# skyboard.net
KiCad netlist of a schematic drawn in EAGLE
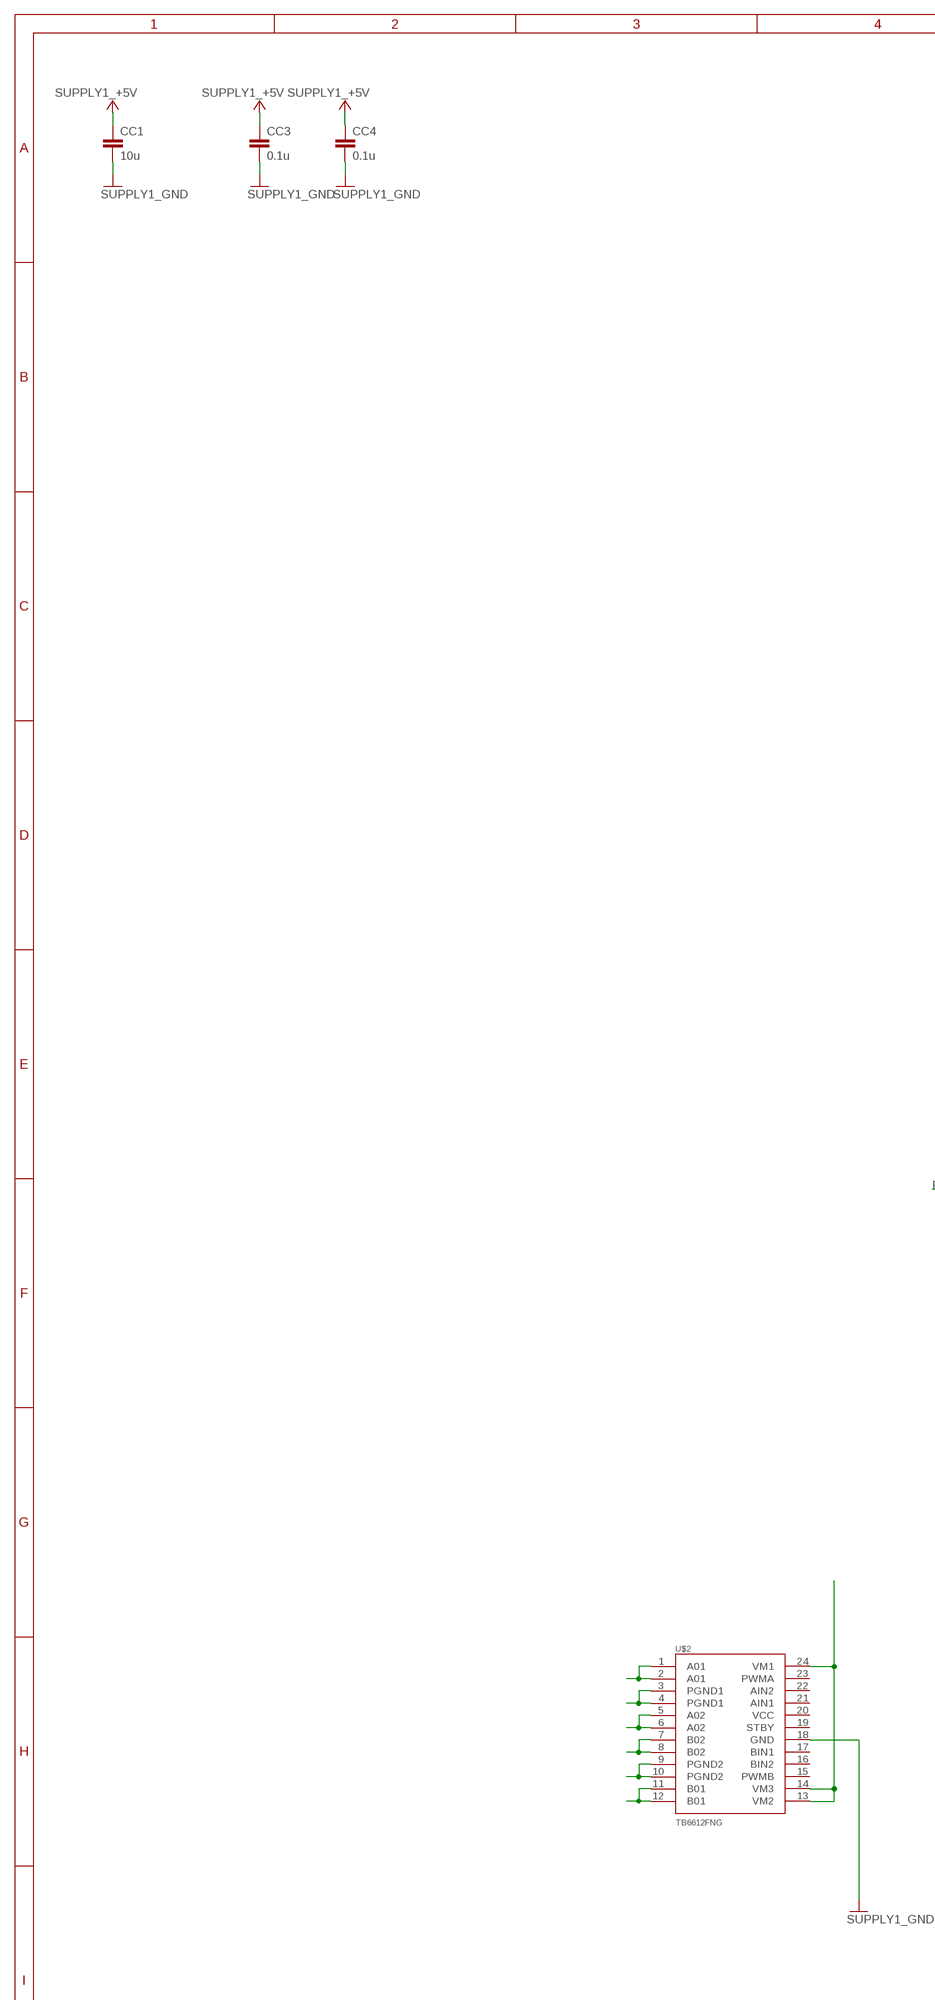
[diagram p0: schematic, sheet 1, part 1 of 2]
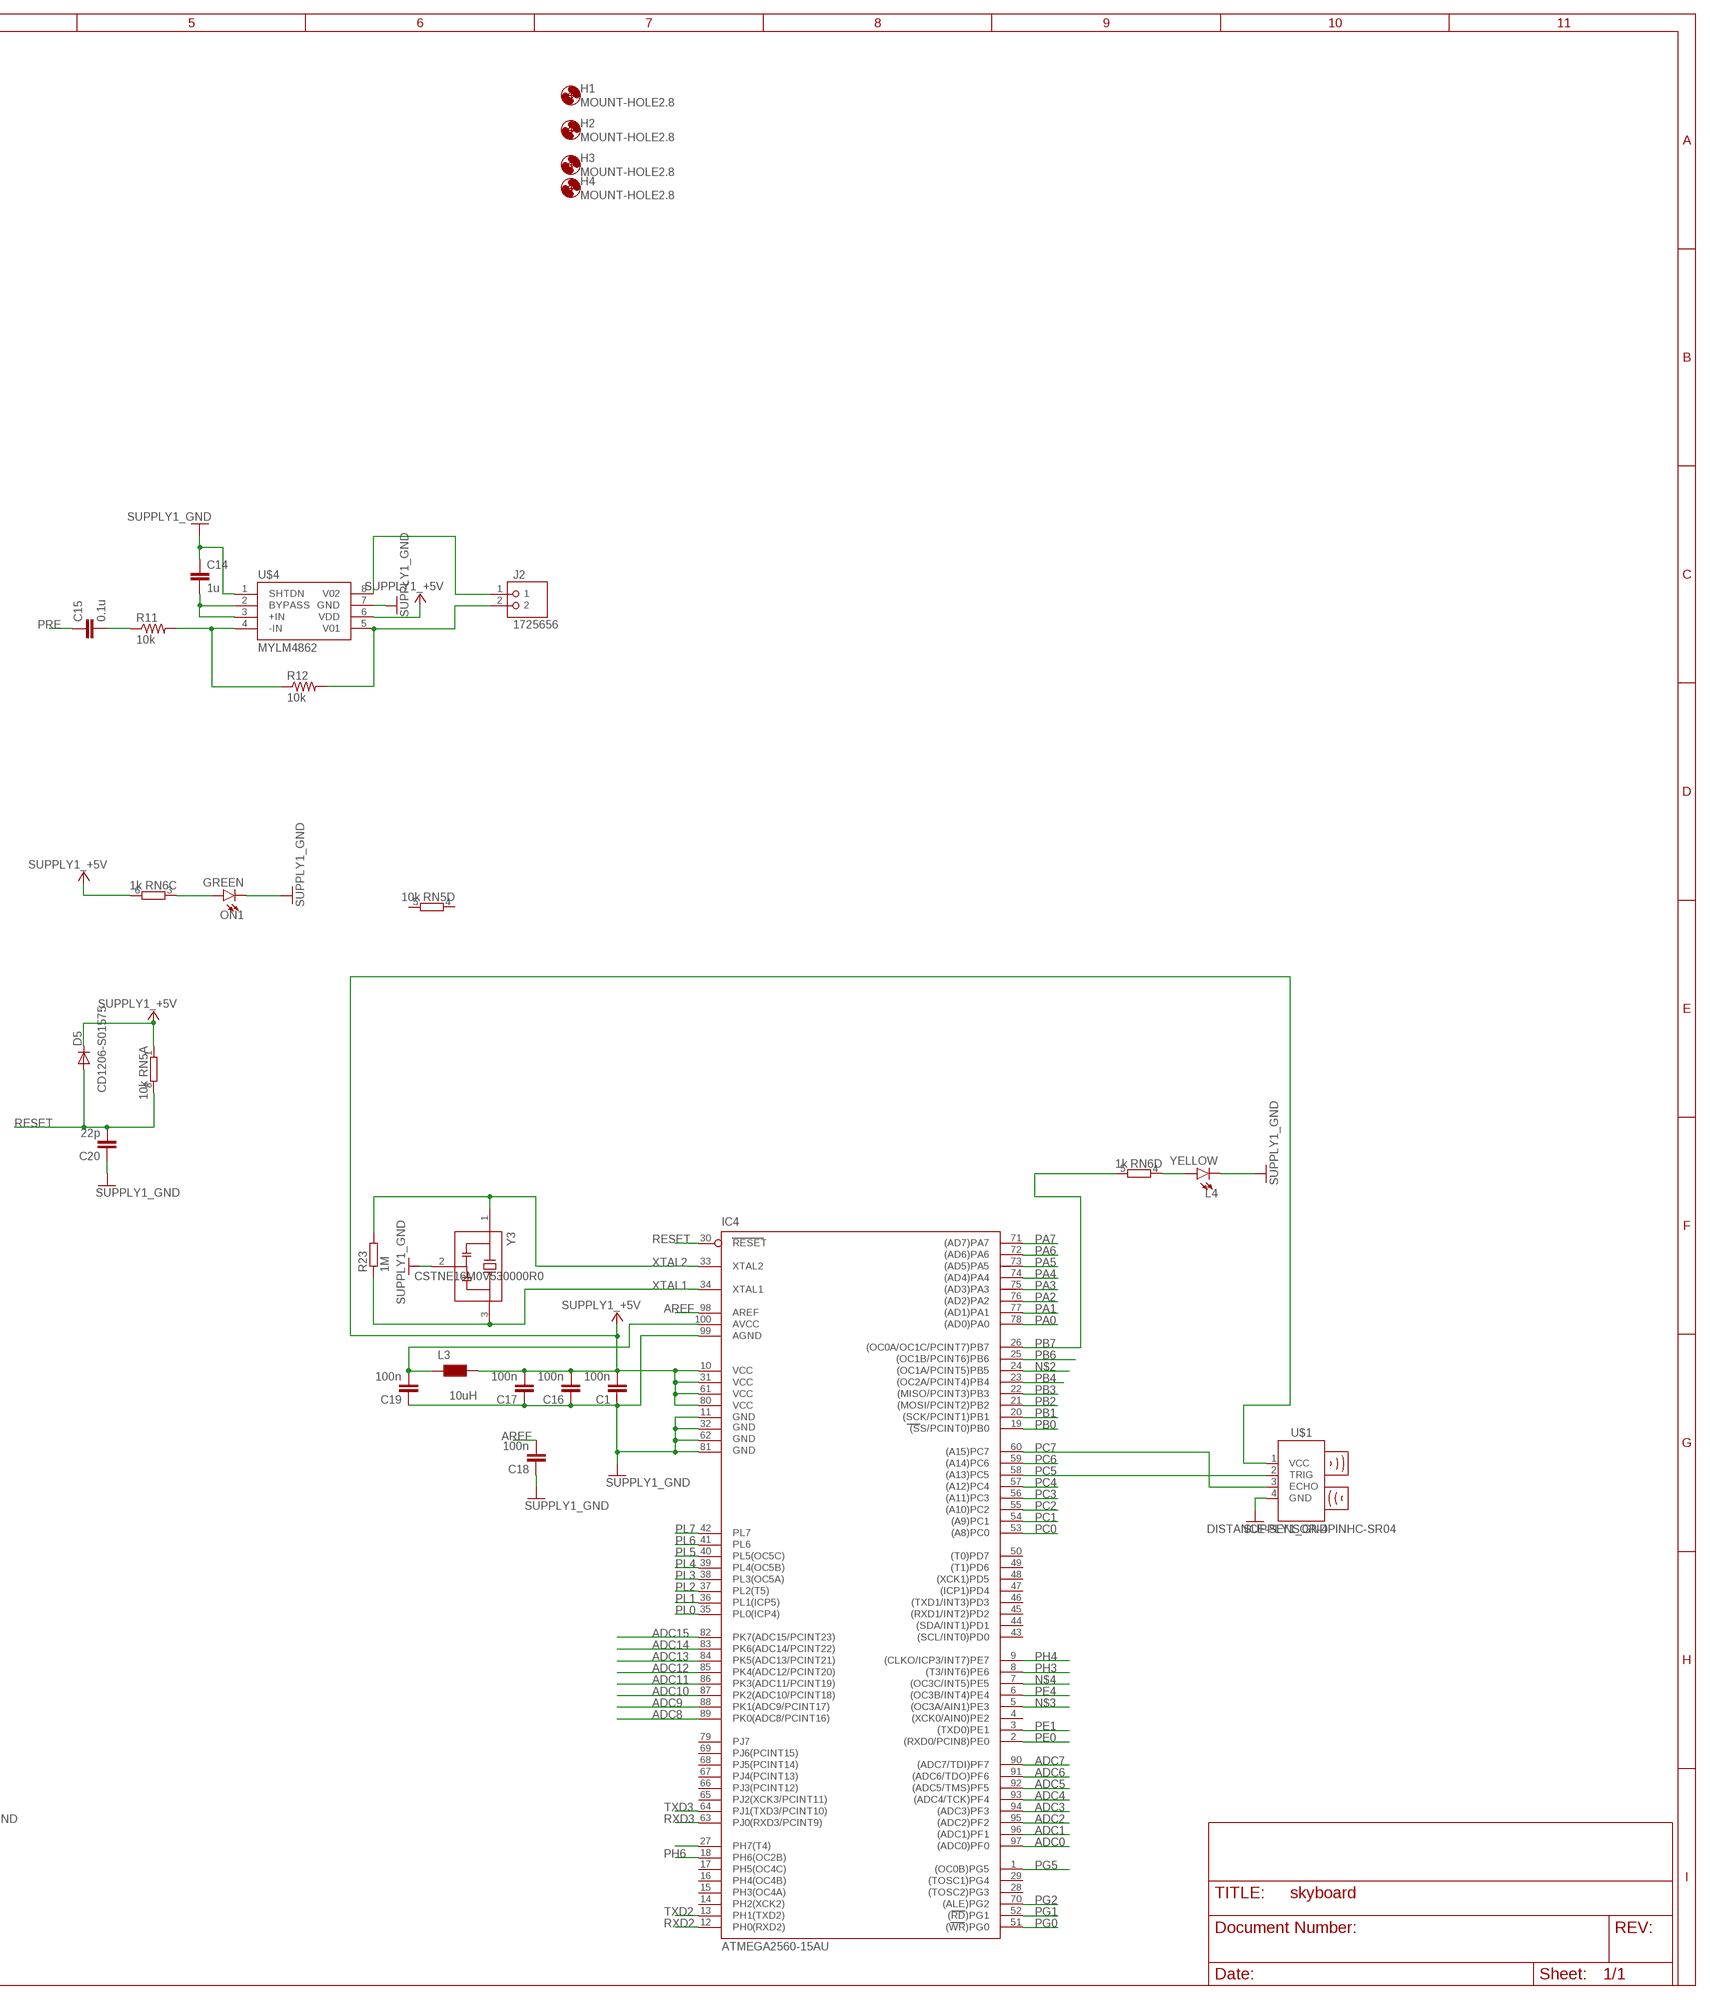
[diagram p1: schematic, sheet 1, part 2 of 2]

(export (version "E")
  (design (tool "Eeschema 10.0.6"))
  (components
    (comp (ref "C1")
      (value "100n")
      (footprint "eagle-import:SMARTPRJ_C1206")
      (libsource (lib "eagle-import") (part "SMARTPRJ_C-EUC1206"))
    )
    (comp (ref "C14")
      (value "1u")
      (footprint "eagle-import:SMARTPRJ_C1206")
      (libsource (lib "eagle-import") (part "SMARTPRJ_C-EUC1206"))
    )
    (comp (ref "C15")
      (value "0.1u")
      (footprint "eagle-import:SMARTPRJ_C1206")
      (libsource (lib "eagle-import") (part "SMARTPRJ_C-EUC1206"))
    )
    (comp (ref "C16")
      (value "100n")
      (footprint "eagle-import:SMARTPRJ_C1206")
      (libsource (lib "eagle-import") (part "SMARTPRJ_C-EUC1206"))
    )
    (comp (ref "C17")
      (value "100n")
      (footprint "eagle-import:SMARTPRJ_C1206")
      (libsource (lib "eagle-import") (part "SMARTPRJ_C-EUC1206"))
    )
    (comp (ref "C18")
      (value "100n")
      (footprint "eagle-import:SMARTPRJ_C1206")
      (libsource (lib "eagle-import") (part "SMARTPRJ_C-EUC1206"))
    )
    (comp (ref "C19")
      (value "100n")
      (footprint "eagle-import:SMARTPRJ_C1206")
      (libsource (lib "eagle-import") (part "SMARTPRJ_C-EUC1206"))
    )
    (comp (ref "C20")
      (value "22p")
      (footprint "eagle-import:SMARTPRJ_C1206")
      (libsource (lib "eagle-import") (part "SMARTPRJ_C-EUC1206"))
    )
    (comp (ref "CC1")
      (value "10u")
      (footprint "eagle-import:SMARTPRJ_C1206")
      (libsource (lib "eagle-import") (part "SMARTPRJ_C-EUC1206"))
    )
    (comp (ref "CC3")
      (value "0.1u")
      (footprint "eagle-import:SMARTPRJ_C1206")
      (libsource (lib "eagle-import") (part "SMARTPRJ_C-EUC1206"))
    )
    (comp (ref "CC4")
      (value "0.1u")
      (footprint "eagle-import:SMARTPRJ_C1206")
      (libsource (lib "eagle-import") (part "SMARTPRJ_C-EUC1206"))
    )
    (comp (ref "D5")
      (value "CD1206-S01575")
      (footprint "eagle-import:DIODE_MINIMELF")
      (libsource (lib "eagle-import") (part "DIODE_DIODE-MINIMELF"))
    )
    (comp (ref "H1")
      (value "MOUNT-HOLE2.8")
      (footprint "eagle-import:2,8")
      (libsource (lib "eagle-import") (part "MOUNT-HOLE2.8"))
    )
    (comp (ref "H2")
      (value "MOUNT-HOLE2.8")
      (footprint "eagle-import:2,8")
      (libsource (lib "eagle-import") (part "MOUNT-HOLE2.8"))
    )
    (comp (ref "H3")
      (value "MOUNT-HOLE2.8")
      (footprint "eagle-import:2,8")
      (libsource (lib "eagle-import") (part "MOUNT-HOLE2.8"))
    )
    (comp (ref "H4")
      (value "MOUNT-HOLE2.8")
      (footprint "eagle-import:2,8")
      (libsource (lib "eagle-import") (part "MOUNT-HOLE2.8"))
    )
    (comp (ref "IC4")
      (value "ATMEGA2560-15AU")
      (footprint "eagle-import:INTEGRATEDCIRCUITS_TQFP100")
      (fields (field (name "PART_NUMBER") "ATMEGA2560-16AU"))
      (libsource (lib "eagle-import") (part "INTEGRATEDCIRCUITS_0023_ATMEGA2560-16AU"))
    )
    (comp (ref "J2")
      (value "1725656")
      (footprint "eagle-import:PHOENIX_1725656")
      (fields (field (name "MANUFACTURER") "Phoenix Contact"))
      (libsource (lib "eagle-import") (part "1725656"))
    )
    (comp (ref "L3")
      (value "10uH")
      (footprint "eagle-import:INDUTTANZE_0805")
      (fields (field (name "PART_NUMBER") "CV201210-100K"))
      (libsource (lib "eagle-import") (part "INDUTTANZE_0715_CV201210-100K"))
    )
    (comp (ref "L4")
      (value "YELLOW")
      (footprint "eagle-import:LED-1206")
      (libsource (lib "eagle-import") (part "LED1206"))
    )
    (comp (ref "ON1")
      (value "GREEN")
      (footprint "eagle-import:LED-1206")
      (libsource (lib "eagle-import") (part "LED1206"))
    )
    (comp (ref "R11")
      (value "10k")
      (footprint "eagle-import:R1206")
      (libsource (lib "eagle-import") (part "R-US_R1206"))
    )
    (comp (ref "R12")
      (value "10k")
      (footprint "eagle-import:R1206")
      (libsource (lib "eagle-import") (part "R-US_R1206"))
    )
    (comp (ref "R23")
      (value "1M")
      (footprint "eagle-import:SMARTPRJ_R1206")
      (libsource (lib "eagle-import") (part "SMARTPRJ_R-EU_R1206"))
    )
    (comp (ref "RN5")
      (value "10k")
      (footprint "eagle-import:RESISTOR-DIL_CAY16")
      (libsource (lib "eagle-import") (part "RESISTOR-DIL_4R-NCAY16"))
    )
    (comp (ref "RN6")
      (value "1k")
      (footprint "eagle-import:RESISTOR-DIL_CAY16")
      (libsource (lib "eagle-import") (part "RESISTOR-DIL_4R-NCAY16"))
    )
    (comp (ref "U$1")
      (value "DISTANCE-SENSOR-4PINHC-SR04")
      (footprint "eagle-import:HC-SR04")
      (libsource (lib "eagle-import") (part "DISTANCE-SENSOR-4PINHC-SR04"))
    )
    (comp (ref "U$2")
      (value "TB6612FNG")
      (footprint "eagle-import:SSOP24")
      (libsource (lib "eagle-import") (part "TB6612FNG"))
    )
    (comp (ref "U$4")
      (value "MYLM4862")
      (footprint "eagle-import:MYSOIC8")
      (libsource (lib "eagle-import") (part "MYLM4862"))
    )
    (comp (ref "Y3")
      (value "CSTNE16M0V530000R0")
      (footprint "eagle-import:OSC_CSTNE16M0V530000R0")
      (fields (field (name "MANUFACTURER") "Murata"))
      (libsource (lib "eagle-import") (part "CSTNE16M0V530000R0"))
    )
  )
  (nets
    (net (code "1") (name "/ADC0") (class "Default")
      (node (ref "IC4") (pin "97") (pinfunction "(ADC0)PF0_97") (pintype "bidirectional"))
    )
    (net (code "2") (name "/ADC1") (class "Default")
      (node (ref "IC4") (pin "96") (pinfunction "(ADC1)PF1_96") (pintype "bidirectional"))
    )
    (net (code "3") (name "/ADC2") (class "Default")
      (node (ref "IC4") (pin "95") (pinfunction "(ADC2)PF2_95") (pintype "bidirectional"))
    )
    (net (code "4") (name "/ADC3") (class "Default")
      (node (ref "IC4") (pin "94") (pinfunction "(ADC3)PF3_94") (pintype "bidirectional"))
    )
    (net (code "5") (name "/ADC4") (class "Default")
      (node (ref "IC4") (pin "93") (pinfunction "(ADC4/TCK)PF4_93") (pintype "bidirectional"))
    )
    (net (code "6") (name "/ADC5") (class "Default")
      (node (ref "IC4") (pin "92") (pinfunction "(ADC5/TMS)PF5_92") (pintype "bidirectional"))
    )
    (net (code "7") (name "/ADC6") (class "Default")
      (node (ref "IC4") (pin "91") (pinfunction "(ADC6/TDO)PF6_91") (pintype "bidirectional"))
    )
    (net (code "8") (name "/ADC7") (class "Default")
      (node (ref "IC4") (pin "90") (pinfunction "(ADC7/TDI)PF7_90") (pintype "bidirectional"))
    )
    (net (code "9") (name "/ADC8") (class "Default")
      (node (ref "IC4") (pin "89") (pinfunction "PK0(ADC8/PCINT16)_89") (pintype "bidirectional"))
    )
    (net (code "10") (name "/ADC9") (class "Default")
      (node (ref "IC4") (pin "88") (pinfunction "PK1(ADC9/PCINT17)_88") (pintype "bidirectional"))
    )
    (net (code "11") (name "/ADC10") (class "Default")
      (node (ref "IC4") (pin "87") (pinfunction "PK2(ADC10/PCINT18)_87") (pintype "bidirectional"))
    )
    (net (code "12") (name "/ADC11") (class "Default")
      (node (ref "IC4") (pin "86") (pinfunction "PK3(ADC11/PCINT19)_86") (pintype "bidirectional"))
    )
    (net (code "13") (name "/ADC12") (class "Default")
      (node (ref "IC4") (pin "85") (pinfunction "PK4(ADC12/PCINT20)_85") (pintype "bidirectional"))
    )
    (net (code "14") (name "/ADC13") (class "Default")
      (node (ref "IC4") (pin "84") (pinfunction "PK5(ADC13/PCINT21)_84") (pintype "bidirectional"))
    )
    (net (code "15") (name "/ADC14") (class "Default")
      (node (ref "IC4") (pin "83") (pinfunction "PK6(ADC14/PCINT22)_83") (pintype "bidirectional"))
    )
    (net (code "16") (name "/ADC15") (class "Default")
      (node (ref "IC4") (pin "82") (pinfunction "PK7(ADC15/PCINT23)_82") (pintype "bidirectional"))
    )
    (net (code "17") (name "/AREF") (class "Default")
      (node (ref "C18") (pin "2") (pinfunction "2_2") (pintype "passive"))
      (node (ref "IC4") (pin "98") (pinfunction "AREF_98") (pintype "bidirectional"))
    )
    (net (code "18") (name "/N$2") (class "Default")
      (node (ref "IC4") (pin "24") (pinfunction "(OC1A/PCINT5)PB5_24") (pintype "bidirectional"))
    )
    (net (code "19") (name "/N$3") (class "Default")
      (node (ref "IC4") (pin "5") (pinfunction "(OC3A/AIN1)PE3_5") (pintype "bidirectional"))
    )
    (net (code "20") (name "/N$4") (class "Default")
      (node (ref "IC4") (pin "7") (pinfunction "(OC3C/INT5)PE5_7") (pintype "bidirectional"))
    )
    (net (code "21") (name "/PA0") (class "Default")
      (node (ref "IC4") (pin "78") (pinfunction "(AD0)PA0_78") (pintype "bidirectional"))
    )
    (net (code "22") (name "/PA1") (class "Default")
      (node (ref "IC4") (pin "77") (pinfunction "(AD1)PA1_77") (pintype "bidirectional"))
    )
    (net (code "23") (name "/PA2") (class "Default")
      (node (ref "IC4") (pin "76") (pinfunction "(AD2)PA2_76") (pintype "bidirectional"))
    )
    (net (code "24") (name "/PA3") (class "Default")
      (node (ref "IC4") (pin "75") (pinfunction "(AD3)PA3_75") (pintype "bidirectional"))
    )
    (net (code "25") (name "/PA4") (class "Default")
      (node (ref "IC4") (pin "74") (pinfunction "(AD4)PA4_74") (pintype "bidirectional"))
    )
    (net (code "26") (name "/PA5") (class "Default")
      (node (ref "IC4") (pin "73") (pinfunction "(AD5)PA5_73") (pintype "bidirectional"))
    )
    (net (code "27") (name "/PA6") (class "Default")
      (node (ref "IC4") (pin "72") (pinfunction "(AD6)PA6_72") (pintype "bidirectional"))
    )
    (net (code "28") (name "/PA7") (class "Default")
      (node (ref "IC4") (pin "71") (pinfunction "(AD7)PA7_71") (pintype "bidirectional"))
    )
    (net (code "29") (name "/PB0") (class "Default")
      (node (ref "IC4") (pin "19") (pinfunction "(SS/PCINT0)PB0_19") (pintype "bidirectional"))
    )
    (net (code "30") (name "/PB1") (class "Default")
      (node (ref "IC4") (pin "20") (pinfunction "(SCK/PCINT1)PB1_20") (pintype "bidirectional"))
    )
    (net (code "31") (name "/PB2") (class "Default")
      (node (ref "IC4") (pin "21") (pinfunction "(MOSI/PCINT2)PB2_21") (pintype "bidirectional"))
    )
    (net (code "32") (name "/PB3") (class "Default")
      (node (ref "IC4") (pin "22") (pinfunction "(MISO/PCINT3)PB3_22") (pintype "bidirectional"))
    )
    (net (code "33") (name "/PB4") (class "Default")
      (node (ref "IC4") (pin "23") (pinfunction "(OC2A/PCINT4)PB4_23") (pintype "bidirectional"))
    )
    (net (code "34") (name "/PB6") (class "Default")
      (node (ref "IC4") (pin "25") (pinfunction "(OC1B/PCINT6)PB6_25") (pintype "bidirectional"))
    )
    (net (code "35") (name "/PB7") (class "Default")
      (node (ref "IC4") (pin "26") (pinfunction "(OC0A/OC1C/PCINT7)PB7_26") (pintype "bidirectional"))
      (node (ref "RN6") (pin "5") (pinfunction "2_5") (pintype "passive"))
    )
    (net (code "36") (name "/PC0") (class "Default")
      (node (ref "IC4") (pin "53") (pinfunction "(A8)PC0_53") (pintype "bidirectional"))
    )
    (net (code "37") (name "/PC1") (class "Default")
      (node (ref "IC4") (pin "54") (pinfunction "(A9)PC1_54") (pintype "bidirectional"))
    )
    (net (code "38") (name "/PC2") (class "Default")
      (node (ref "IC4") (pin "55") (pinfunction "(A10)PC2_55") (pintype "bidirectional"))
    )
    (net (code "39") (name "/PC3") (class "Default")
      (node (ref "IC4") (pin "56") (pinfunction "(A11)PC3_56") (pintype "bidirectional"))
    )
    (net (code "40") (name "/PC4") (class "Default")
      (node (ref "IC4") (pin "57") (pinfunction "(A12)PC4_57") (pintype "bidirectional"))
    )
    (net (code "41") (name "/PC5") (class "Default")
      (node (ref "IC4") (pin "58") (pinfunction "(A13)PC5_58") (pintype "bidirectional"))
      (node (ref "U$1") (pin "2") (pinfunction "TRIG_2") (pintype "bidirectional"))
    )
    (net (code "42") (name "/PC6") (class "Default")
      (node (ref "IC4") (pin "59") (pinfunction "(A14)PC6_59") (pintype "bidirectional"))
    )
    (net (code "43") (name "/PC7") (class "Default")
      (node (ref "IC4") (pin "60") (pinfunction "(A15)PC7_60") (pintype "bidirectional"))
      (node (ref "U$1") (pin "3") (pinfunction "ECHO_3") (pintype "bidirectional"))
    )
    (net (code "44") (name "/PE0") (class "Default")
      (node (ref "IC4") (pin "2") (pinfunction "(RXD0/PCIN8)PE0_2") (pintype "bidirectional"))
    )
    (net (code "45") (name "/PE1") (class "Default")
      (node (ref "IC4") (pin "3") (pinfunction "(TXD0)PE1_3") (pintype "bidirectional"))
    )
    (net (code "46") (name "/PE4") (class "Default")
      (node (ref "IC4") (pin "6") (pinfunction "(OC3B/INT4)PE4_6") (pintype "bidirectional"))
    )
    (net (code "47") (name "/PG0") (class "Default")
      (node (ref "IC4") (pin "51") (pinfunction "(WR)PG0_51") (pintype "bidirectional"))
    )
    (net (code "48") (name "/PG1") (class "Default")
      (node (ref "IC4") (pin "52") (pinfunction "(RD)PG1_52") (pintype "bidirectional"))
    )
    (net (code "49") (name "/PG2") (class "Default")
      (node (ref "IC4") (pin "70") (pinfunction "(ALE)PG2_70") (pintype "bidirectional"))
    )
    (net (code "50") (name "/PG5") (class "Default")
      (node (ref "IC4") (pin "1") (pinfunction "(OC0B)PG5_1") (pintype "bidirectional"))
    )
    (net (code "51") (name "/PH3") (class "Default")
      (node (ref "IC4") (pin "8") (pinfunction "(T3/INT6)PE6_8") (pintype "bidirectional"))
    )
    (net (code "52") (name "/PH4") (class "Default")
      (node (ref "IC4") (pin "9") (pinfunction "(CLKO/ICP3/INT7)PE7_9") (pintype "bidirectional"))
    )
    (net (code "53") (name "/PH6") (class "Default")
      (node (ref "IC4") (pin "18") (pinfunction "PH6(OC2B)_18") (pintype "bidirectional"))
    )
    (net (code "54") (name "/PL0") (class "Default")
      (node (ref "IC4") (pin "35") (pinfunction "PL0(ICP4)_35") (pintype "bidirectional"))
    )
    (net (code "55") (name "/PL1") (class "Default")
      (node (ref "IC4") (pin "36") (pinfunction "PL1(ICP5)_36") (pintype "bidirectional"))
    )
    (net (code "56") (name "/PL2") (class "Default")
      (node (ref "IC4") (pin "37") (pinfunction "PL2(T5)_37") (pintype "bidirectional"))
    )
    (net (code "57") (name "/PL3") (class "Default")
      (node (ref "IC4") (pin "38") (pinfunction "PL3(OC5A)_38") (pintype "bidirectional"))
    )
    (net (code "58") (name "/PL4") (class "Default")
      (node (ref "IC4") (pin "39") (pinfunction "PL4(OC5B)_39") (pintype "bidirectional"))
    )
    (net (code "59") (name "/PL5") (class "Default")
      (node (ref "IC4") (pin "40") (pinfunction "PL5(OC5C)_40") (pintype "bidirectional"))
    )
    (net (code "60") (name "/PL6") (class "Default")
      (node (ref "IC4") (pin "41") (pinfunction "PL6_41") (pintype "bidirectional"))
    )
    (net (code "61") (name "/PL7") (class "Default")
      (node (ref "IC4") (pin "42") (pinfunction "PL7_42") (pintype "bidirectional"))
    )
    (net (code "62") (name "/PRE") (class "Default")
      (node (ref "C15") (pin "1") (pinfunction "1_1") (pintype "passive"))
    )
    (net (code "63") (name "/RESET") (class "Default")
      (node (ref "C20") (pin "2") (pinfunction "2_2") (pintype "passive"))
      (node (ref "D5") (pin "A") (pinfunction "A_A") (pintype "passive"))
      (node (ref "IC4") (pin "30") (pinfunction "RESET_30") (pintype "input"))
      (node (ref "RN5") (pin "8") (pinfunction "2_8") (pintype "passive"))
    )
    (net (code "64") (name "/RXD2") (class "Default")
      (node (ref "IC4") (pin "12") (pinfunction "PH0(RXD2)_12") (pintype "bidirectional"))
    )
    (net (code "65") (name "/RXD3") (class "Default")
      (node (ref "IC4") (pin "63") (pinfunction "PJ0(RXD3/PCINT9)_63") (pintype "bidirectional"))
    )
    (net (code "66") (name "/TXD2") (class "Default")
      (node (ref "IC4") (pin "13") (pinfunction "PH1(TXD2)_13") (pintype "bidirectional"))
    )
    (net (code "67") (name "/TXD3") (class "Default")
      (node (ref "IC4") (pin "64") (pinfunction "PJ1(TXD3/PCINT10)_64") (pintype "bidirectional"))
    )
    (net (code "68") (name "/XTAL1") (class "Default")
      (node (ref "IC4") (pin "34") (pinfunction "XTAL1_34") (pintype "input"))
      (node (ref "R23") (pin "1") (pinfunction "1_1") (pintype "passive"))
      (node (ref "Y3") (pin "3") (pinfunction "OUT_3") (pintype "output"))
    )
    (net (code "69") (name "/XTAL2") (class "Default")
      (node (ref "IC4") (pin "33") (pinfunction "XTAL2_33") (pintype "output"))
      (node (ref "R23") (pin "2") (pinfunction "2_2") (pintype "passive"))
      (node (ref "Y3") (pin "1") (pinfunction "IN_1") (pintype "input"))
    )
    (net (code "70") (name "Net-(C15-Pad2)") (class "Default")
      (node (ref "C15") (pin "2") (pinfunction "2_2") (pintype "passive"))
      (node (ref "R11") (pin "1") (pinfunction "1_1") (pintype "passive"))
    )
    (net (code "71") (name "Net-(IC4-AVCC)") (class "Default")
      (node (ref "C19") (pin "2") (pinfunction "2_2") (pintype "passive"))
      (node (ref "IC4") (pin "100") (pinfunction "AVCC_100") (pintype "power_in"))
      (node (ref "L3") (pin "1") (pinfunction "1_1") (pintype "passive"))
    )
    (net (code "72") (name "Net-(RN6C-1)") (class "Default")
      (node (ref "ON1") (pin "A") (pinfunction "A_A") (pintype "passive"))
      (node (ref "RN6") (pin "3") (pinfunction "1_3") (pintype "passive"))
    )
    (net (code "73") (name "Net-(RN6D-1)") (class "Default")
      (node (ref "L4") (pin "A") (pinfunction "A_A") (pintype "passive"))
      (node (ref "RN6") (pin "4") (pinfunction "1_4") (pintype "passive"))
    )
    (net (code "74") (name "Net-(U$2-A01-Pad1)") (class "Default")
      (node (ref "U$2") (pin "1") (pinfunction "A01_1") (pintype "bidirectional"))
      (node (ref "U$2") (pin "2") (pinfunction "A01_2") (pintype "bidirectional"))
    )
    (net (code "75") (name "Net-(U$2-A02-Pad5)") (class "Default")
      (node (ref "U$2") (pin "5") (pinfunction "A02_5") (pintype "bidirectional"))
      (node (ref "U$2") (pin "6") (pinfunction "A02_6") (pintype "bidirectional"))
    )
    (net (code "76") (name "Net-(U$2-B01-Pad11)") (class "Default")
      (node (ref "U$2") (pin "11") (pinfunction "B01_11") (pintype "bidirectional"))
      (node (ref "U$2") (pin "12") (pinfunction "B01_12") (pintype "bidirectional"))
    )
    (net (code "77") (name "Net-(U$2-B02-Pad7)") (class "Default")
      (node (ref "U$2") (pin "7") (pinfunction "B02_7") (pintype "bidirectional"))
      (node (ref "U$2") (pin "8") (pinfunction "B02_8") (pintype "bidirectional"))
    )
    (net (code "78") (name "Net-(U$2-PGND1-Pad3)") (class "Default")
      (node (ref "U$2") (pin "3") (pinfunction "PGND1_3") (pintype "bidirectional"))
      (node (ref "U$2") (pin "4") (pinfunction "PGND1_4") (pintype "bidirectional"))
    )
    (net (code "79") (name "Net-(U$2-PGND2-Pad10)") (class "Default")
      (node (ref "U$2") (pin "10") (pinfunction "PGND2_10") (pintype "bidirectional"))
      (node (ref "U$2") (pin "9") (pinfunction "PGND2_9") (pintype "bidirectional"))
    )
    (net (code "80") (name "Net-(U$2-VM1)") (class "Default")
      (node (ref "U$2") (pin "13") (pinfunction "VM2_13") (pintype "bidirectional"))
      (node (ref "U$2") (pin "14") (pinfunction "VM3_14") (pintype "bidirectional"))
      (node (ref "U$2") (pin "24") (pinfunction "VM1_24") (pintype "bidirectional"))
    )
    (net (code "81") (name "Net-(U$4-+IN)") (class "Default")
      (node (ref "C14") (pin "2") (pinfunction "2_2") (pintype "passive"))
      (node (ref "U$4") (pin "2") (pinfunction "BYPASS_2") (pintype "bidirectional"))
      (node (ref "U$4") (pin "3") (pinfunction "+IN_3") (pintype "bidirectional"))
    )
    (net (code "82") (name "Net-(U$4--IN)") (class "Default")
      (node (ref "R11") (pin "2") (pinfunction "2_2") (pintype "passive"))
      (node (ref "R12") (pin "1") (pinfunction "1_1") (pintype "passive"))
      (node (ref "U$4") (pin "4") (pinfunction "-IN_4") (pintype "power_in"))
    )
    (net (code "83") (name "Net-(U$4-V01)") (class "Default")
      (node (ref "J2") (pin "2") (pinfunction "2_2") (pintype "passive"))
      (node (ref "R12") (pin "2") (pinfunction "2_2") (pintype "passive"))
      (node (ref "U$4") (pin "5") (pinfunction "V01_5") (pintype "bidirectional"))
    )
    (net (code "84") (name "Net-(U$4-V02)") (class "Default")
      (node (ref "J2") (pin "1") (pinfunction "1_1") (pintype "passive"))
      (node (ref "U$4") (pin "8") (pinfunction "V02_8") (pintype "power_in"))
    )
    (net (code "85") (name "SUPPLY1_+5V") (class "Default")
      (node (ref "C1") (pin "2") (pinfunction "2_2") (pintype "passive"))
      (node (ref "C16") (pin "2") (pinfunction "2_2") (pintype "passive"))
      (node (ref "C17") (pin "2") (pinfunction "2_2") (pintype "passive"))
      (node (ref "CC1") (pin "1") (pinfunction "1_1") (pintype "passive"))
      (node (ref "CC3") (pin "1") (pinfunction "1_1") (pintype "passive"))
      (node (ref "CC4") (pin "1") (pinfunction "1_1") (pintype "passive"))
      (node (ref "D5") (pin "C") (pinfunction "C_C") (pintype "passive"))
      (node (ref "IC4") (pin "10") (pinfunction "VCC_10") (pintype "power_in"))
      (node (ref "IC4") (pin "31") (pinfunction "VCC1_31") (pintype "power_in"))
      (node (ref "IC4") (pin "61") (pinfunction "VCC2_61") (pintype "power_in"))
      (node (ref "IC4") (pin "80") (pinfunction "VCC3_80") (pintype "power_in"))
      (node (ref "L3") (pin "2") (pinfunction "2_2") (pintype "passive"))
      (node (ref "RN5") (pin "1") (pinfunction "1_1") (pintype "passive"))
      (node (ref "RN6") (pin "6") (pinfunction "2_6") (pintype "passive"))
      (node (ref "U$1") (pin "1") (pinfunction "VCC_1") (pintype "bidirectional"))
      (node (ref "U$4") (pin "6") (pinfunction "VDD_6") (pintype "bidirectional"))
    )
    (net (code "86") (name "SUPPLY1_GND") (class "Default")
      (node (ref "C1") (pin "1") (pinfunction "1_1") (pintype "passive"))
      (node (ref "C14") (pin "1") (pinfunction "1_1") (pintype "passive"))
      (node (ref "C16") (pin "1") (pinfunction "1_1") (pintype "passive"))
      (node (ref "C17") (pin "1") (pinfunction "1_1") (pintype "passive"))
      (node (ref "C18") (pin "1") (pinfunction "1_1") (pintype "passive"))
      (node (ref "C19") (pin "1") (pinfunction "1_1") (pintype "passive"))
      (node (ref "C20") (pin "1") (pinfunction "1_1") (pintype "passive"))
      (node (ref "CC1") (pin "2") (pinfunction "2_2") (pintype "passive"))
      (node (ref "CC3") (pin "2") (pinfunction "2_2") (pintype "passive"))
      (node (ref "CC4") (pin "2") (pinfunction "2_2") (pintype "passive"))
      (node (ref "IC4") (pin "11") (pinfunction "GND_11") (pintype "power_in"))
      (node (ref "IC4") (pin "32") (pinfunction "GND1_32") (pintype "power_in"))
      (node (ref "IC4") (pin "62") (pinfunction "GND2_62") (pintype "power_in"))
      (node (ref "IC4") (pin "81") (pinfunction "GND3_81") (pintype "power_in"))
      (node (ref "IC4") (pin "99") (pinfunction "AGND_99") (pintype "power_in"))
      (node (ref "L4") (pin "C") (pinfunction "C_C") (pintype "passive"))
      (node (ref "ON1") (pin "C") (pinfunction "C_C") (pintype "passive"))
      (node (ref "U$1") (pin "4") (pinfunction "GND_4") (pintype "bidirectional"))
      (node (ref "U$2") (pin "18") (pinfunction "GND_18") (pintype "bidirectional"))
      (node (ref "U$4") (pin "1") (pinfunction "SHTDN_1") (pintype "bidirectional"))
      (node (ref "U$4") (pin "7") (pinfunction "GND_7") (pintype "bidirectional"))
      (node (ref "Y3") (pin "2") (pinfunction "GND_2") (pintype "power_in"))
    )
    (net (code "87") (name "unconnected-(IC4-(ICP1)PD4-Pad47)") (class "Default")
      (node (ref "IC4") (pin "47") (pinfunction "(ICP1)PD4_47") (pintype "bidirectional"))
    )
    (net (code "88") (name "unconnected-(IC4-(RXD1{slash}INT2)PD2-Pad45)") (class "Default")
      (node (ref "IC4") (pin "45") (pinfunction "(RXD1/INT2)PD2_45") (pintype "bidirectional"))
    )
    (net (code "89") (name "unconnected-(IC4-(SCL{slash}INT0)PD0-Pad43)") (class "Default")
      (node (ref "IC4") (pin "43") (pinfunction "(SCL/INT0)PD0_43") (pintype "bidirectional"))
    )
    (net (code "90") (name "unconnected-(IC4-(SDA{slash}INT1)PD1-Pad44)") (class "Default")
      (node (ref "IC4") (pin "44") (pinfunction "(SDA/INT1)PD1_44") (pintype "bidirectional"))
    )
    (net (code "91") (name "unconnected-(IC4-(T0)PD7-Pad50)") (class "Default")
      (node (ref "IC4") (pin "50") (pinfunction "(T0)PD7_50") (pintype "bidirectional"))
    )
    (net (code "92") (name "unconnected-(IC4-(T1)PD6-Pad49)") (class "Default")
      (node (ref "IC4") (pin "49") (pinfunction "(T1)PD6_49") (pintype "bidirectional"))
    )
    (net (code "93") (name "unconnected-(IC4-(TOSC1)PG4-Pad29)") (class "Default")
      (node (ref "IC4") (pin "29") (pinfunction "(TOSC1)PG4_29") (pintype "bidirectional"))
    )
    (net (code "94") (name "unconnected-(IC4-(TOSC2)PG3-Pad28)") (class "Default")
      (node (ref "IC4") (pin "28") (pinfunction "(TOSC2)PG3_28") (pintype "bidirectional"))
    )
    (net (code "95") (name "unconnected-(IC4-(TXD1{slash}INT3)PD3-Pad46)") (class "Default")
      (node (ref "IC4") (pin "46") (pinfunction "(TXD1/INT3)PD3_46") (pintype "bidirectional"))
    )
    (net (code "96") (name "unconnected-(IC4-(XCK0{slash}AIN0)PE2-Pad4)") (class "Default")
      (node (ref "IC4") (pin "4") (pinfunction "(XCK0/AIN0)PE2_4") (pintype "bidirectional"))
    )
    (net (code "97") (name "unconnected-(IC4-(XCK1)PD5-Pad48)") (class "Default")
      (node (ref "IC4") (pin "48") (pinfunction "(XCK1)PD5_48") (pintype "bidirectional"))
    )
    (net (code "98") (name "unconnected-(IC4-PH2(XCK2)-Pad14)") (class "Default")
      (node (ref "IC4") (pin "14") (pinfunction "PH2(XCK2)_14") (pintype "bidirectional"))
    )
    (net (code "99") (name "unconnected-(IC4-PH3(OC4A)-Pad15)") (class "Default")
      (node (ref "IC4") (pin "15") (pinfunction "PH3(OC4A)_15") (pintype "bidirectional"))
    )
    (net (code "100") (name "unconnected-(IC4-PH4(OC4B)-Pad16)") (class "Default")
      (node (ref "IC4") (pin "16") (pinfunction "PH4(OC4B)_16") (pintype "bidirectional"))
    )
    (net (code "101") (name "unconnected-(IC4-PH5(OC4C)-Pad17)") (class "Default")
      (node (ref "IC4") (pin "17") (pinfunction "PH5(OC4C)_17") (pintype "bidirectional"))
    )
    (net (code "102") (name "unconnected-(IC4-PH7(T4)-Pad27)") (class "Default")
      (node (ref "IC4") (pin "27") (pinfunction "PH7(T4)_27") (pintype "bidirectional"))
    )
    (net (code "103") (name "unconnected-(IC4-PJ2(XCK3{slash}PCINT11)-Pad65)") (class "Default")
      (node (ref "IC4") (pin "65") (pinfunction "PJ2(XCK3/PCINT11)_65") (pintype "bidirectional"))
    )
    (net (code "104") (name "unconnected-(IC4-PJ3(PCINT12)-Pad66)") (class "Default")
      (node (ref "IC4") (pin "66") (pinfunction "PJ3(PCINT12)_66") (pintype "bidirectional"))
    )
    (net (code "105") (name "unconnected-(IC4-PJ4(PCINT13)-Pad67)") (class "Default")
      (node (ref "IC4") (pin "67") (pinfunction "PJ4(PCINT13)_67") (pintype "bidirectional"))
    )
    (net (code "106") (name "unconnected-(IC4-PJ5(PCINT14)-Pad68)") (class "Default")
      (node (ref "IC4") (pin "68") (pinfunction "PJ5(PCINT14)_68") (pintype "bidirectional"))
    )
    (net (code "107") (name "unconnected-(IC4-PJ6(PCINT15)-Pad69)") (class "Default")
      (node (ref "IC4") (pin "69") (pinfunction "PJ6(PCINT15)_69") (pintype "bidirectional"))
    )
    (net (code "108") (name "unconnected-(IC4-PJ7-Pad79)") (class "Default")
      (node (ref "IC4") (pin "79") (pinfunction "PJ7_79") (pintype "bidirectional"))
    )
    (net (code "109") (name "unconnected-(RN5D-1-Pad4)") (class "Default")
      (node (ref "RN5") (pin "4") (pinfunction "1_4") (pintype "passive"))
    )
    (net (code "110") (name "unconnected-(RN5D-2-Pad5)") (class "Default")
      (node (ref "RN5") (pin "5") (pinfunction "2_5") (pintype "passive"))
    )
    (net (code "111") (name "unconnected-(U$2-AIN1-Pad21)") (class "Default")
      (node (ref "U$2") (pin "21") (pinfunction "AIN1_21") (pintype "bidirectional"))
    )
    (net (code "112") (name "unconnected-(U$2-AIN2-Pad22)") (class "Default")
      (node (ref "U$2") (pin "22") (pinfunction "AIN2_22") (pintype "bidirectional"))
    )
    (net (code "113") (name "unconnected-(U$2-BIN1-Pad17)") (class "Default")
      (node (ref "U$2") (pin "17") (pinfunction "BIN1_17") (pintype "bidirectional"))
    )
    (net (code "114") (name "unconnected-(U$2-BIN2-Pad16)") (class "Default")
      (node (ref "U$2") (pin "16") (pinfunction "BIN2_16") (pintype "bidirectional"))
    )
    (net (code "115") (name "unconnected-(U$2-PWMA-Pad23)") (class "Default")
      (node (ref "U$2") (pin "23") (pinfunction "PWMA_23") (pintype "bidirectional"))
    )
    (net (code "116") (name "unconnected-(U$2-PWMB-Pad15)") (class "Default")
      (node (ref "U$2") (pin "15") (pinfunction "PWMB_15") (pintype "bidirectional"))
    )
    (net (code "117") (name "unconnected-(U$2-STBY-Pad19)") (class "Default")
      (node (ref "U$2") (pin "19") (pinfunction "STBY_19") (pintype "bidirectional"))
    )
    (net (code "118") (name "unconnected-(U$2-VCC-Pad20)") (class "Default")
      (node (ref "U$2") (pin "20") (pinfunction "VCC_20") (pintype "bidirectional"))
    )
  )
)
